# TMK-EURO-0_1_1x.net
KiCad netlist of a schematic drawn in EAGLE
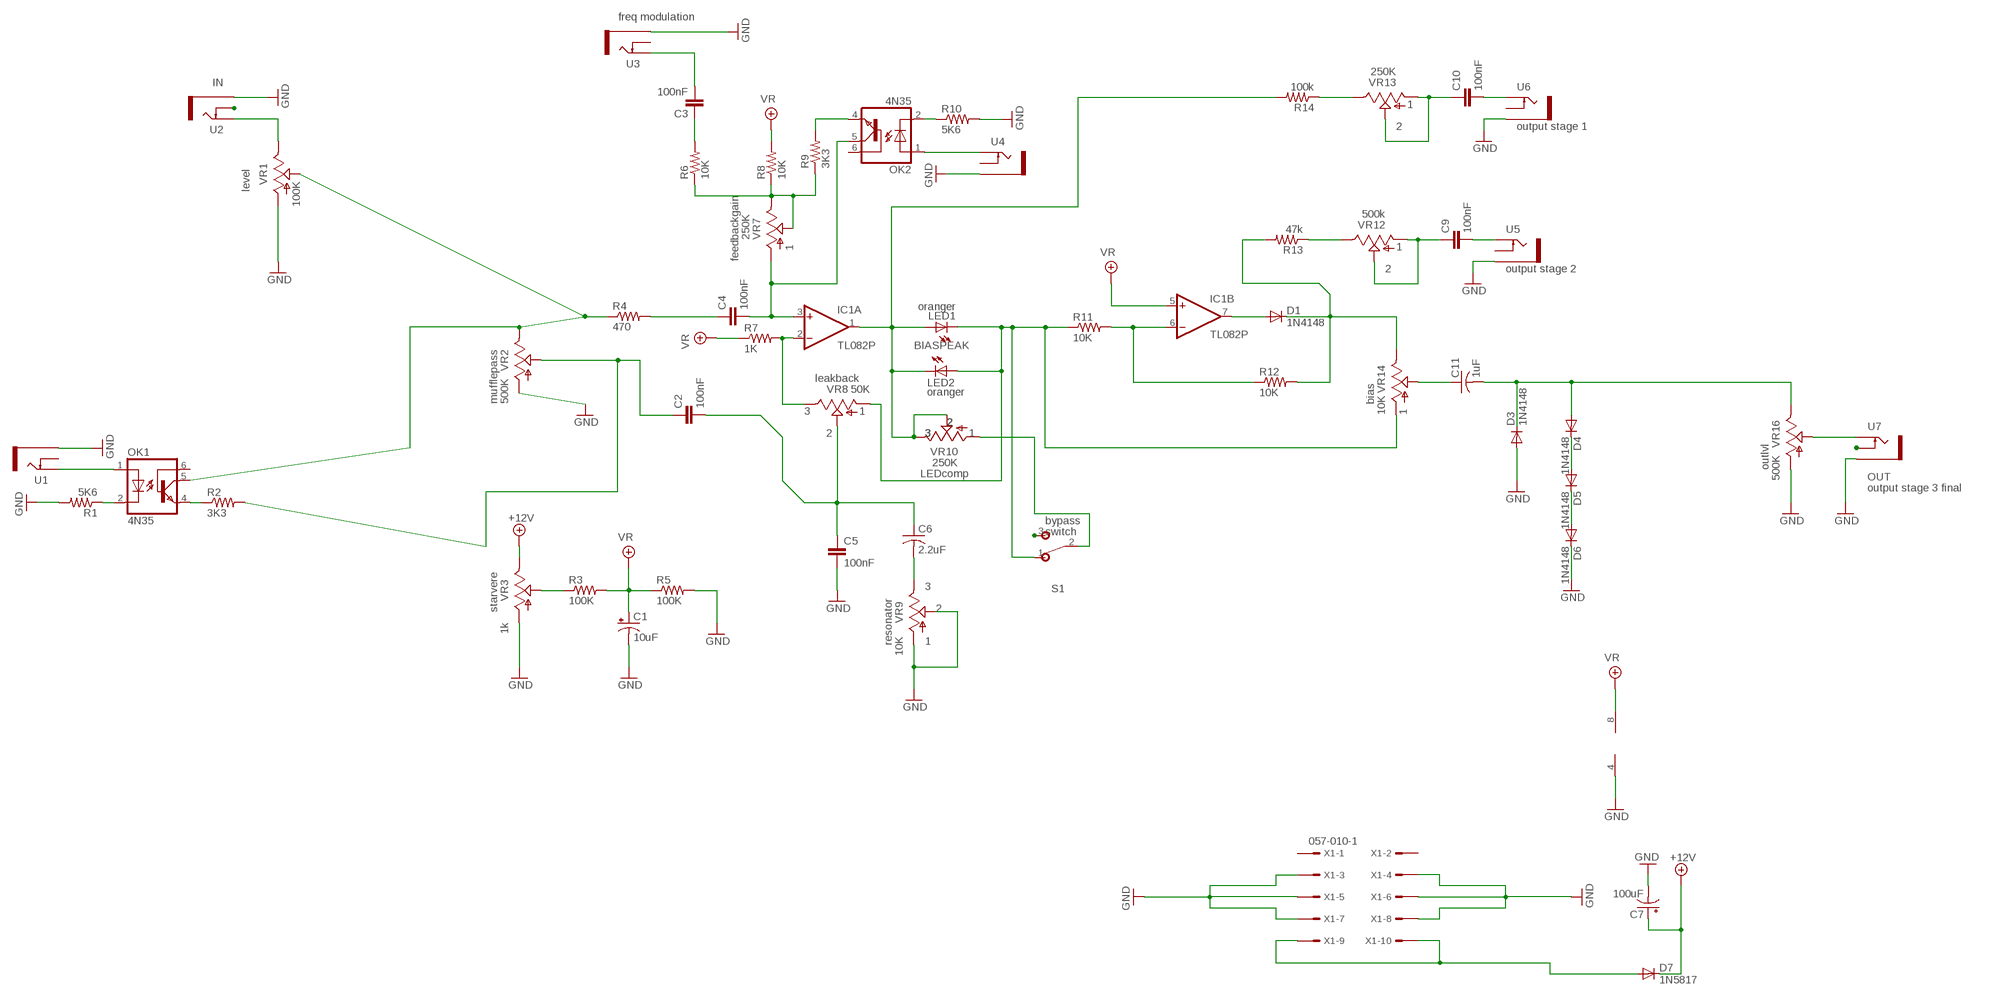
[diagram p0: schematic, sheet 1]

(export (version "E")
  (design (tool "Eeschema 10.0.6"))
  (components
    (comp (ref "C1")
      (value "10uF")
      (footprint "eagle-import:E2-5")
      (libsource (lib "eagle-import") (part "CPOL-USE2-5"))
    )
    (comp (ref "C2")
      (value "100nF")
      (footprint "eagle-import:C050-035X075")
      (libsource (lib "eagle-import") (part "C-EU050-035X075"))
    )
    (comp (ref "C3")
      (value "100nF")
      (footprint "eagle-import:C050-035X075")
      (libsource (lib "eagle-import") (part "C-EU050-035X075"))
    )
    (comp (ref "C4")
      (value "100nF")
      (footprint "eagle-import:C050-035X075")
      (libsource (lib "eagle-import") (part "C-EU050-035X075"))
    )
    (comp (ref "C5")
      (value "100nF")
      (footprint "eagle-import:C050-035X075")
      (libsource (lib "eagle-import") (part "C-EU050-035X075"))
    )
    (comp (ref "C6")
      (value "2.2uF")
      (footprint "eagle-import:C050-030X075")
      (libsource (lib "eagle-import") (part "C-US050-030X075"))
    )
    (comp (ref "C7")
      (value "100uF")
      (footprint "eagle-import:080_035")
      (libsource (lib "eagle-import") (part "080"))
    )
    (comp (ref "C9")
      (value "100nF")
      (footprint "eagle-import:C050-035X075")
      (libsource (lib "eagle-import") (part "C-EU050-035X075"))
    )
    (comp (ref "C10")
      (value "100nF")
      (footprint "eagle-import:C050-035X075")
      (libsource (lib "eagle-import") (part "C-EU050-035X075"))
    )
    (comp (ref "C11")
      (value "1uF")
      (footprint "eagle-import:C050-075X075")
      (libsource (lib "eagle-import") (part "C-US050-075X075"))
    )
    (comp (ref "D1")
      (value "1N4148")
      (footprint "eagle-import:DO35-7")
      (libsource (lib "eagle-import") (part "SMALL_DIODEDO35-7"))
    )
    (comp (ref "D3")
      (value "1N4148")
      (footprint "eagle-import:DO35-7")
      (libsource (lib "eagle-import") (part "SMALL_DIODEDO35-7"))
    )
    (comp (ref "D4")
      (value "1N4148")
      (footprint "eagle-import:DO35-7")
      (libsource (lib "eagle-import") (part "SMALL_DIODEDO35-7"))
    )
    (comp (ref "D5")
      (value "1N4148")
      (footprint "eagle-import:DO35-7")
      (libsource (lib "eagle-import") (part "SMALL_DIODEDO35-7"))
    )
    (comp (ref "D6")
      (value "1N4148")
      (footprint "eagle-import:DO35-7")
      (libsource (lib "eagle-import") (part "SMALL_DIODEDO35-7"))
    )
    (comp (ref "D7")
      (value "1N5817")
      (footprint "eagle-import:DO35-7")
      (libsource (lib "eagle-import") (part "SMALL_DIODEDO35-7"))
    )
    (comp (ref "IC1")
      (value "TL082P")
      (footprint "eagle-import:DIL08")
      (libsource (lib "eagle-import") (part "TL082P"))
    )
    (comp (ref "LED1")
      (value "oranger")
      (footprint "eagle-import:LED3MM")
      (libsource (lib "eagle-import") (part "LED3MM"))
    )
    (comp (ref "LED2")
      (value "oranger")
      (footprint "eagle-import:LED3MM")
      (libsource (lib "eagle-import") (part "LED3MM"))
    )
    (comp (ref "OK1")
      (value "4N35")
      (footprint "eagle-import:DIL06")
      (fields (field (name "MF") "FAIRCHILD SEMICONDUCTOR"))
      (libsource (lib "eagle-import") (part "4N35"))
    )
    (comp (ref "OK2")
      (value "4N35")
      (footprint "eagle-import:DIL06")
      (fields (field (name "MF") "FAIRCHILD SEMICONDUCTOR"))
      (libsource (lib "eagle-import") (part "4N35"))
    )
    (comp (ref "R1")
      (value "5K6")
      (footprint "eagle-import:0207_7")
      (libsource (lib "eagle-import") (part "R-US_0207/7"))
    )
    (comp (ref "R2")
      (value "3K3")
      (footprint "eagle-import:0207_7")
      (libsource (lib "eagle-import") (part "R-US_0207/7"))
    )
    (comp (ref "R3")
      (value "100K")
      (footprint "eagle-import:0207_7")
      (libsource (lib "eagle-import") (part "R-US_0207/7"))
    )
    (comp (ref "R4")
      (value "470")
      (footprint "eagle-import:0207_7")
      (libsource (lib "eagle-import") (part "R-US_0207/7"))
    )
    (comp (ref "R5")
      (value "100K")
      (footprint "eagle-import:0207_7")
      (libsource (lib "eagle-import") (part "R-US_0207/7"))
    )
    (comp (ref "R6")
      (value "10K")
      (footprint "eagle-import:0207_7")
      (libsource (lib "eagle-import") (part "R-US_0207/7"))
    )
    (comp (ref "R7")
      (value "1K")
      (footprint "eagle-import:0207_7")
      (libsource (lib "eagle-import") (part "R-US_0207/7"))
    )
    (comp (ref "R8")
      (value "10K")
      (footprint "eagle-import:0207_7")
      (libsource (lib "eagle-import") (part "R-US_0207/7"))
    )
    (comp (ref "R9")
      (value "3K3")
      (footprint "eagle-import:0207_7")
      (libsource (lib "eagle-import") (part "R-US_0207/7"))
    )
    (comp (ref "R10")
      (value "5K6")
      (footprint "eagle-import:0207_7")
      (libsource (lib "eagle-import") (part "R-US_0207/7"))
    )
    (comp (ref "R11")
      (value "10K")
      (footprint "eagle-import:0207_7")
      (libsource (lib "eagle-import") (part "R-US_0207/7"))
    )
    (comp (ref "R12")
      (value "10K")
      (footprint "eagle-import:0207_7")
      (libsource (lib "eagle-import") (part "R-US_0207/7"))
    )
    (comp (ref "R13")
      (value "47k")
      (footprint "eagle-import:0207_7")
      (libsource (lib "eagle-import") (part "R-US_0207/7"))
    )
    (comp (ref "R14")
      (value "100k")
      (footprint "eagle-import:0207_7")
      (libsource (lib "eagle-import") (part "R-US_0207/7"))
    )
    (comp (ref "S1")
      (value "SPDTPADS")
      (footprint "eagle-import:SPDT")
      (libsource (lib "eagle-import") (part "SPDTPADS"))
    )
    (comp (ref "U1")
      (value "IN")
      (footprint "eagle-import:THONKICONN")
      (libsource (lib "eagle-import") (part "THONKICONNOLD"))
    )
    (comp (ref "U2")
      (value "IN")
      (footprint "eagle-import:THONKICONN")
      (libsource (lib "eagle-import") (part "THONKICONNOLD"))
    )
    (comp (ref "U3")
      (value "IN")
      (footprint "eagle-import:THONKICONN")
      (libsource (lib "eagle-import") (part "THONKICONNOLD"))
    )
    (comp (ref "U4")
      (value "IN")
      (footprint "eagle-import:THONKICONN")
      (libsource (lib "eagle-import") (part "THONKICONNOLD"))
    )
    (comp (ref "U5")
      (value "IN")
      (footprint "eagle-import:THONKICONN")
      (libsource (lib "eagle-import") (part "THONKICONNOLD"))
    )
    (comp (ref "U6")
      (value "IN")
      (footprint "eagle-import:THONKICONN")
      (libsource (lib "eagle-import") (part "THONKICONNOLD"))
    )
    (comp (ref "U7")
      (value "THONKICONNOLD")
      (footprint "eagle-import:THONKICONN")
      (libsource (lib "eagle-import") (part "THONKICONNOLD"))
    )
    (comp (ref "VR1")
      (value "100K")
      (footprint "eagle-import:9MM_SNAP-IN_POT")
      (libsource (lib "eagle-import") (part "9MM_SNAP-IN_POT_"))
    )
    (comp (ref "VR2")
      (value "500K")
      (footprint "eagle-import:9MM_SNAP-IN_POT")
      (libsource (lib "eagle-import") (part "9MM_SNAP-IN_POT_"))
    )
    (comp (ref "VR3")
      (value "1k")
      (footprint "eagle-import:9MM_SNAP-IN_POT")
      (libsource (lib "eagle-import") (part "9MM_SNAP-IN_POT_"))
    )
    (comp (ref "VR7")
      (value "250K")
      (footprint "eagle-import:9MM_SNAP-IN_POT")
      (libsource (lib "eagle-import") (part "9MM_SNAP-IN_POT_"))
    )
    (comp (ref "VR8")
      (value "50K")
      (footprint "eagle-import:9MM_SNAP-IN_POT")
      (libsource (lib "eagle-import") (part "9MM_SNAP-IN_POT_"))
    )
    (comp (ref "VR9")
      (value "10K")
      (footprint "eagle-import:9MM_SNAP-IN_POT")
      (libsource (lib "eagle-import") (part "9MM_SNAP-IN_POT_"))
    )
    (comp (ref "VR10")
      (value "250K")
      (footprint "eagle-import:9MM_SNAP-IN_POT")
      (libsource (lib "eagle-import") (part "9MM_SNAP-IN_POT_"))
    )
    (comp (ref "VR12")
      (value "500k")
      (footprint "eagle-import:9MM_SNAP-IN_POT")
      (libsource (lib "eagle-import") (part "9MM_SNAP-IN_POT_"))
    )
    (comp (ref "VR13")
      (value "250K")
      (footprint "eagle-import:9MM_SNAP-IN_POT")
      (libsource (lib "eagle-import") (part "9MM_SNAP-IN_POT_"))
    )
    (comp (ref "VR14")
      (value "10K")
      (footprint "eagle-import:9MM_SNAP-IN_POT")
      (libsource (lib "eagle-import") (part "9MM_SNAP-IN_POT_"))
    )
    (comp (ref "VR16")
      (value "500K")
      (footprint "eagle-import:9MM_SNAP-IN_POT")
      (libsource (lib "eagle-import") (part "9MM_SNAP-IN_POT_"))
    )
    (comp (ref "X1")
      (value "057-010-1")
      (footprint "eagle-import:057-010-1")
      (libsource (lib "eagle-import") (part "057-010-1"))
    )
  )
  (nets
    (net (code "1") (name "+12V") (class "Default")
      (node (ref "C7") (pin "+") (pinfunction "+_+") (pintype "passive"))
      (node (ref "D7") (pin "C") (pinfunction "C_C") (pintype "passive"))
      (node (ref "VR3") (pin "3") (pinfunction "E_3") (pintype "passive"))
    )
    (net (code "2") (name "GND") (class "Default")
      (node (ref "C1") (pin "-") (pinfunction "-_-") (pintype "passive"))
      (node (ref "C5") (pin "2") (pinfunction "2_2") (pintype "passive"))
      (node (ref "C7") (pin "-") (pinfunction "-_-") (pintype "passive"))
      (node (ref "D3") (pin "A") (pinfunction "A_A") (pintype "passive"))
      (node (ref "D6") (pin "C") (pinfunction "C_C") (pintype "passive"))
      (node (ref "IC1") (pin "4") (pinfunction "V-_4") (pintype "power_in"))
      (node (ref "R1") (pin "2") (pinfunction "2_2") (pintype "passive"))
      (node (ref "R10") (pin "2") (pinfunction "2_2") (pintype "passive"))
      (node (ref "R5") (pin "2") (pinfunction "2_2") (pintype "passive"))
      (node (ref "U1") (pin "P$1_SLEEVE") (pinfunction "SLEEVE_P$1_SLEEVE") (pintype "passive"))
      (node (ref "U2") (pin "P$1_SLEEVE") (pinfunction "SLEEVE_P$1_SLEEVE") (pintype "passive"))
      (node (ref "U3") (pin "P$1_SLEEVE") (pinfunction "SLEEVE_P$1_SLEEVE") (pintype "passive"))
      (node (ref "U4") (pin "P$1_SLEEVE") (pinfunction "SLEEVE_P$1_SLEEVE") (pintype "passive"))
      (node (ref "U5") (pin "P$1_SLEEVE") (pinfunction "SLEEVE_P$1_SLEEVE") (pintype "passive"))
      (node (ref "U6") (pin "P$1_SLEEVE") (pinfunction "SLEEVE_P$1_SLEEVE") (pintype "passive"))
      (node (ref "U7") (pin "P$1_SLEEVE") (pinfunction "SLEEVE_P$1_SLEEVE") (pintype "passive"))
      (node (ref "VR1") (pin "1") (pinfunction "A_1") (pintype "passive"))
      (node (ref "VR16") (pin "1") (pinfunction "A_1") (pintype "passive"))
      (node (ref "VR2") (pin "1") (pinfunction "A_1") (pintype "passive"))
      (node (ref "VR3") (pin "1") (pinfunction "A_1") (pintype "passive"))
      (node (ref "VR9") (pin "1") (pinfunction "A_1") (pintype "passive"))
      (node (ref "VR9") (pin "2") (pinfunction "S_2") (pintype "passive"))
      (node (ref "X1") (pin "3") (pinfunction "S_3") (pintype "passive"))
      (node (ref "X1") (pin "4") (pinfunction "S_4") (pintype "passive"))
      (node (ref "X1") (pin "5") (pinfunction "S_5") (pintype "passive"))
      (node (ref "X1") (pin "6") (pinfunction "S_6") (pintype "passive"))
      (node (ref "X1") (pin "7") (pinfunction "S_7") (pintype "passive"))
      (node (ref "X1") (pin "8") (pinfunction "S_8") (pintype "passive"))
    )
    (net (code "3") (name "Net-(C3-Pad1)") (class "Default")
      (node (ref "C3") (pin "1") (pinfunction "1_1") (pintype "passive"))
      (node (ref "R6") (pin "2") (pinfunction "2_2") (pintype "passive"))
    )
    (net (code "4") (name "Net-(C4-Pad1)") (class "Default")
      (node (ref "C4") (pin "1") (pinfunction "1_1") (pintype "passive"))
      (node (ref "R4") (pin "2") (pinfunction "2_2") (pintype "passive"))
    )
    (net (code "5") (name "Net-(D4-PadC)") (class "Default")
      (node (ref "D4") (pin "C") (pinfunction "C_C") (pintype "passive"))
      (node (ref "D5") (pin "A") (pinfunction "A_A") (pintype "passive"))
    )
    (net (code "6") (name "Net-(D5-PadC)") (class "Default")
      (node (ref "D5") (pin "C") (pinfunction "C_C") (pintype "passive"))
      (node (ref "D6") (pin "A") (pinfunction "A_A") (pintype "passive"))
    )
    (net (code "7") (name "Net-(IC1A-+IN)") (class "Default")
      (node (ref "C4") (pin "2") (pinfunction "2_2") (pintype "passive"))
      (node (ref "IC1") (pin "3") (pinfunction "+IN_3") (pintype "input"))
      (node (ref "OK2") (pin "5") (pinfunction "COL_5") (pintype "passive"))
      (node (ref "VR7") (pin "1") (pinfunction "A_1") (pintype "passive"))
    )
    (net (code "8") (name "Net-(IC1A--IN)") (class "Default")
      (node (ref "IC1") (pin "2") (pinfunction "-IN_2") (pintype "input"))
      (node (ref "R7") (pin "2") (pinfunction "2_2") (pintype "passive"))
      (node (ref "VR8") (pin "3") (pinfunction "E_3") (pintype "passive"))
    )
    (net (code "9") (name "Net-(IC1A-OUT)") (class "Default")
      (node (ref "IC1") (pin "1") (pinfunction "OUT_1") (pintype "output"))
      (node (ref "LED1") (pin "A") (pinfunction "A_A") (pintype "passive"))
      (node (ref "LED2") (pin "K") (pinfunction "C_K") (pintype "passive"))
      (node (ref "R14") (pin "2") (pinfunction "2_2") (pintype "passive"))
      (node (ref "VR10") (pin "2") (pinfunction "S_2") (pintype "passive"))
      (node (ref "VR10") (pin "3") (pinfunction "E_3") (pintype "passive"))
    )
    (net (code "10") (name "Net-(IC1B--IN)") (class "Default")
      (node (ref "IC1") (pin "6") (pinfunction "-IN_6") (pintype "input"))
      (node (ref "R11") (pin "2") (pinfunction "2_2") (pintype "passive"))
      (node (ref "R12") (pin "1") (pinfunction "1_1") (pintype "passive"))
    )
    (net (code "11") (name "Net-(IC1B-OUT)") (class "Default")
      (node (ref "D1") (pin "A") (pinfunction "A_A") (pintype "passive"))
      (node (ref "IC1") (pin "7") (pinfunction "OUT_7") (pintype "output"))
    )
    (net (code "12") (name "Net-(LED1-C)") (class "Default")
      (node (ref "LED1") (pin "K") (pinfunction "C_K") (pintype "passive"))
      (node (ref "LED2") (pin "A") (pinfunction "A_A") (pintype "passive"))
      (node (ref "R11") (pin "1") (pinfunction "1_1") (pintype "passive"))
      (node (ref "S1") (pin "1") (pinfunction "O_1") (pintype "passive"))
      (node (ref "VR14") (pin "1") (pinfunction "A_1") (pintype "passive"))
      (node (ref "VR8") (pin "1") (pinfunction "A_1") (pintype "passive"))
    )
    (net (code "13") (name "Net-(OK1-A)") (class "Default")
      (node (ref "OK1") (pin "1") (pinfunction "A_1") (pintype "passive"))
      (node (ref "U1") (pin "P$3_TIP") (pinfunction "TIP_P$3_TIP") (pintype "passive"))
    )
    (net (code "14") (name "Net-(OK1-C)") (class "Default")
      (node (ref "OK1") (pin "2") (pinfunction "C_2") (pintype "passive"))
      (node (ref "R1") (pin "1") (pinfunction "1_1") (pintype "passive"))
    )
    (net (code "15") (name "Net-(OK1-COL)") (class "Default")
      (node (ref "OK1") (pin "5") (pinfunction "COL_5") (pintype "passive"))
      (node (ref "R4") (pin "1") (pinfunction "1_1") (pintype "passive"))
      (node (ref "VR1") (pin "2") (pinfunction "S_2") (pintype "passive"))
      (node (ref "VR2") (pin "3") (pinfunction "E_3") (pintype "passive"))
    )
    (net (code "16") (name "Net-(OK1-EMI)") (class "Default")
      (node (ref "OK1") (pin "4") (pinfunction "EMI_4") (pintype "passive"))
      (node (ref "R2") (pin "1") (pinfunction "1_1") (pintype "passive"))
    )
    (net (code "17") (name "Net-(OK2-A)") (class "Default")
      (node (ref "OK2") (pin "1") (pinfunction "A_1") (pintype "passive"))
      (node (ref "U4") (pin "P$3_TIP") (pinfunction "TIP_P$3_TIP") (pintype "passive"))
    )
    (net (code "18") (name "Net-(OK2-C)") (class "Default")
      (node (ref "OK2") (pin "2") (pinfunction "C_2") (pintype "passive"))
      (node (ref "R10") (pin "1") (pinfunction "1_1") (pintype "passive"))
    )
    (net (code "19") (name "Net-(OK2-EMI)") (class "Default")
      (node (ref "OK2") (pin "4") (pinfunction "EMI_4") (pintype "passive"))
      (node (ref "R9") (pin "2") (pinfunction "2_2") (pintype "passive"))
    )
    (net (code "20") (name "Net-(S1-P)") (class "Default")
      (node (ref "S1") (pin "2") (pinfunction "P_2") (pintype "passive"))
      (node (ref "VR10") (pin "1") (pinfunction "A_1") (pintype "passive"))
    )
    (net (code "21") (name "Net-(U2-TIP)") (class "Default")
      (node (ref "U2") (pin "P$3_TIP") (pinfunction "TIP_P$3_TIP") (pintype "passive"))
      (node (ref "VR1") (pin "3") (pinfunction "E_3") (pintype "passive"))
    )
    (net (code "22") (name "Net-(U3-TIP)") (class "Default")
      (node (ref "C3") (pin "2") (pinfunction "2_2") (pintype "passive"))
      (node (ref "U3") (pin "P$3_TIP") (pinfunction "TIP_P$3_TIP") (pintype "passive"))
    )
    (net (code "23") (name "Net-(U5-TIP)") (class "Default")
      (node (ref "C9") (pin "2") (pinfunction "2_2") (pintype "passive"))
      (node (ref "U5") (pin "P$3_TIP") (pinfunction "TIP_P$3_TIP") (pintype "passive"))
    )
    (net (code "24") (name "Net-(U6-TIP)") (class "Default")
      (node (ref "C10") (pin "2") (pinfunction "2_2") (pintype "passive"))
      (node (ref "U6") (pin "P$3_TIP") (pinfunction "TIP_P$3_TIP") (pintype "passive"))
    )
    (net (code "25") (name "Net-(U7-TIP)") (class "Default")
      (node (ref "U7") (pin "P$3_TIP") (pinfunction "TIP_P$3_TIP") (pintype "passive"))
      (node (ref "VR16") (pin "2") (pinfunction "S_2") (pintype "passive"))
    )
    (net (code "26") (name "Net-(VR2-S)") (class "Default")
      (node (ref "C2") (pin "1") (pinfunction "1_1") (pintype "passive"))
      (node (ref "R2") (pin "2") (pinfunction "2_2") (pintype "passive"))
      (node (ref "VR2") (pin "2") (pinfunction "S_2") (pintype "passive"))
    )
    (net (code "27") (name "Net-(VR3-S)") (class "Default")
      (node (ref "R3") (pin "1") (pinfunction "1_1") (pintype "passive"))
      (node (ref "VR3") (pin "2") (pinfunction "S_2") (pintype "passive"))
    )
    (net (code "28") (name "Net-(VR7-E)") (class "Default")
      (node (ref "R6") (pin "1") (pinfunction "1_1") (pintype "passive"))
      (node (ref "R8") (pin "1") (pinfunction "1_1") (pintype "passive"))
      (node (ref "R9") (pin "1") (pinfunction "1_1") (pintype "passive"))
      (node (ref "VR7") (pin "2") (pinfunction "S_2") (pintype "passive"))
      (node (ref "VR7") (pin "3") (pinfunction "E_3") (pintype "passive"))
    )
    (net (code "29") (name "Net-(VR8-S)") (class "Default")
      (node (ref "C2") (pin "2") (pinfunction "2_2") (pintype "passive"))
      (node (ref "C5") (pin "1") (pinfunction "1_1") (pintype "passive"))
      (node (ref "C6") (pin "1") (pinfunction "1_1") (pintype "passive"))
      (node (ref "VR8") (pin "2") (pinfunction "S_2") (pintype "passive"))
    )
    (net (code "30") (name "Net-(VR9-E)") (class "Default")
      (node (ref "C6") (pin "2") (pinfunction "2_2") (pintype "passive"))
      (node (ref "VR9") (pin "3") (pinfunction "E_3") (pintype "passive"))
    )
    (net (code "31") (name "Net-(VR12-A)") (class "Default")
      (node (ref "C9") (pin "1") (pinfunction "1_1") (pintype "passive"))
      (node (ref "VR12") (pin "1") (pinfunction "A_1") (pintype "passive"))
      (node (ref "VR12") (pin "2") (pinfunction "S_2") (pintype "passive"))
    )
    (net (code "32") (name "Net-(VR12-E)") (class "Default")
      (node (ref "R13") (pin "1") (pinfunction "1_1") (pintype "passive"))
      (node (ref "VR12") (pin "3") (pinfunction "E_3") (pintype "passive"))
    )
    (net (code "33") (name "Net-(VR13-A)") (class "Default")
      (node (ref "C10") (pin "1") (pinfunction "1_1") (pintype "passive"))
      (node (ref "VR13") (pin "1") (pinfunction "A_1") (pintype "passive"))
      (node (ref "VR13") (pin "2") (pinfunction "S_2") (pintype "passive"))
    )
    (net (code "34") (name "Net-(VR13-E)") (class "Default")
      (node (ref "R14") (pin "1") (pinfunction "1_1") (pintype "passive"))
      (node (ref "VR13") (pin "3") (pinfunction "E_3") (pintype "passive"))
    )
    (net (code "35") (name "Net-(VR14-E)") (class "Default")
      (node (ref "D1") (pin "C") (pinfunction "C_C") (pintype "passive"))
      (node (ref "R12") (pin "2") (pinfunction "2_2") (pintype "passive"))
      (node (ref "R13") (pin "2") (pinfunction "2_2") (pintype "passive"))
      (node (ref "VR14") (pin "3") (pinfunction "E_3") (pintype "passive"))
    )
    (net (code "36") (name "Net-(VR14-S)") (class "Default")
      (node (ref "C11") (pin "1") (pinfunction "1_1") (pintype "passive"))
      (node (ref "VR14") (pin "2") (pinfunction "S_2") (pintype "passive"))
    )
    (net (code "37") (name "Net-(VR16-E)") (class "Default")
      (node (ref "C11") (pin "2") (pinfunction "2_2") (pintype "passive"))
      (node (ref "D3") (pin "C") (pinfunction "C_C") (pintype "passive"))
      (node (ref "D4") (pin "A") (pinfunction "A_A") (pintype "passive"))
      (node (ref "VR16") (pin "3") (pinfunction "E_3") (pintype "passive"))
    )
    (net (code "38") (name "Net-(X1B-S)") (class "Default")
      (node (ref "D7") (pin "A") (pinfunction "A_A") (pintype "passive"))
      (node (ref "X1") (pin "10") (pinfunction "S_10") (pintype "passive"))
      (node (ref "X1") (pin "9") (pinfunction "S_9") (pintype "passive"))
    )
    (net (code "39") (name "VR") (class "Default")
      (node (ref "C1") (pin "+") (pinfunction "+_+") (pintype "passive"))
      (node (ref "IC1") (pin "5") (pinfunction "+IN_5") (pintype "input"))
      (node (ref "IC1") (pin "8") (pinfunction "V+_8") (pintype "power_in"))
      (node (ref "R3") (pin "2") (pinfunction "2_2") (pintype "passive"))
      (node (ref "R5") (pin "1") (pinfunction "1_1") (pintype "passive"))
      (node (ref "R7") (pin "1") (pinfunction "1_1") (pintype "passive"))
      (node (ref "R8") (pin "2") (pinfunction "2_2") (pintype "passive"))
    )
    (net (code "40") (name "unconnected-(OK1-BAS-Pad6)") (class "Default")
      (node (ref "OK1") (pin "6") (pinfunction "BAS_6") (pintype "passive"))
    )
    (net (code "41") (name "unconnected-(OK2-BAS-Pad6)") (class "Default")
      (node (ref "OK2") (pin "6") (pinfunction "BAS_6") (pintype "passive"))
    )
    (net (code "42") (name "unconnected-(S1-S-Pad3)") (class "Default")
      (node (ref "S1") (pin "3") (pinfunction "S_3") (pintype "passive"))
    )
    (net (code "43") (name "unconnected-(U1-SWITCH-PadP$2_SWITCH)") (class "Default")
      (node (ref "U1") (pin "P$2_SWITCH") (pinfunction "SWITCH_P$2_SWITCH") (pintype "passive"))
    )
    (net (code "44") (name "unconnected-(U2-SWITCH-PadP$2_SWITCH)") (class "Default")
      (node (ref "U2") (pin "P$2_SWITCH") (pinfunction "SWITCH_P$2_SWITCH") (pintype "passive"))
    )
    (net (code "45") (name "unconnected-(U3-SWITCH-PadP$2_SWITCH)") (class "Default")
      (node (ref "U3") (pin "P$2_SWITCH") (pinfunction "SWITCH_P$2_SWITCH") (pintype "passive"))
    )
    (net (code "46") (name "unconnected-(U4-SWITCH-PadP$2_SWITCH)") (class "Default")
      (node (ref "U4") (pin "P$2_SWITCH") (pinfunction "SWITCH_P$2_SWITCH") (pintype "passive"))
    )
    (net (code "47") (name "unconnected-(U5-SWITCH-PadP$2_SWITCH)") (class "Default")
      (node (ref "U5") (pin "P$2_SWITCH") (pinfunction "SWITCH_P$2_SWITCH") (pintype "passive"))
    )
    (net (code "48") (name "unconnected-(U6-SWITCH-PadP$2_SWITCH)") (class "Default")
      (node (ref "U6") (pin "P$2_SWITCH") (pinfunction "SWITCH_P$2_SWITCH") (pintype "passive"))
    )
    (net (code "49") (name "unconnected-(U7-SWITCH-PadP$2_SWITCH)") (class "Default")
      (node (ref "U7") (pin "P$2_SWITCH") (pinfunction "SWITCH_P$2_SWITCH") (pintype "passive"))
    )
    (net (code "50") (name "unconnected-(X1A-S-Pad1)") (class "Default")
      (node (ref "X1") (pin "1") (pinfunction "S_1") (pintype "passive"))
    )
    (net (code "51") (name "unconnected-(X1C-S-Pad2)") (class "Default")
      (node (ref "X1") (pin "2") (pinfunction "S_2") (pintype "passive"))
    )
  )
)
